# Input_1.net
KiCad netlist of a schematic drawn in Altium Designer
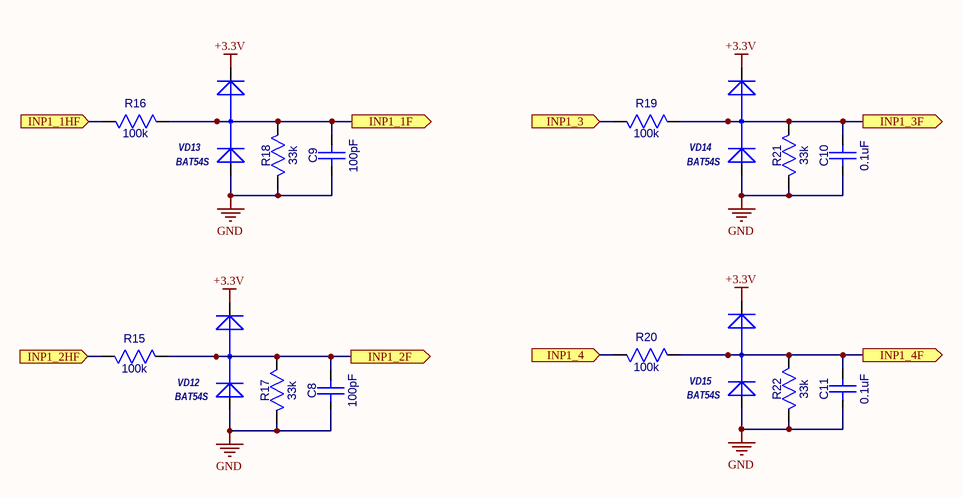
[diagram p0: Input_1.SchDoc]

(export (version "E")
  (design (tool "Eeschema 10.0.6"))
  (components
    (comp (ref "C8")
      (value "100pF")
      (footprint "CC0603-3M")
      (description "CC0603")
      (libsource (lib "*") (part "CC0603"))
    )
    (comp (ref "C9")
      (value "100pF")
      (footprint "CC0603-3M")
      (description "CC0603")
      (libsource (lib "*") (part "CC0603"))
    )
    (comp (ref "C10")
      (value "0.1uF")
      (footprint "CC0603-3M")
      (description "CC0603")
      (libsource (lib "*") (part "CC0603"))
    )
    (comp (ref "C11")
      (value "0.1uF")
      (footprint "CC0603-3M")
      (description "CC0603")
      (libsource (lib "*") (part "CC0603"))
    )
    (comp (ref "R15")
      (value "100k")
      (footprint "RC0603-3M")
      (description "RC0603")
      (libsource (lib "*") (part "RC0603"))
    )
    (comp (ref "R16")
      (value "100k")
      (footprint "RC0603-3M")
      (description "RC0603")
      (libsource (lib "*") (part "RC0603"))
    )
    (comp (ref "R17")
      (value "33k")
      (footprint "RC0603-3M")
      (description "RC0603")
      (libsource (lib "*") (part "RC0603"))
    )
    (comp (ref "R18")
      (value "33k")
      (footprint "RC0603-3M")
      (description "RC0603")
      (libsource (lib "*") (part "RC0603"))
    )
    (comp (ref "R19")
      (value "100k")
      (footprint "RC0603-3M")
      (description "RC0603")
      (libsource (lib "*") (part "RC0603"))
    )
    (comp (ref "R20")
      (value "100k")
      (footprint "RC0603-3M")
      (description "RC0603")
      (libsource (lib "*") (part "RC0603"))
    )
    (comp (ref "R21")
      (value "33k")
      (footprint "RC0603-3M")
      (description "RC0603")
      (libsource (lib "*") (part "RC0603"))
    )
    (comp (ref "R22")
      (value "33k")
      (footprint "RC0603-3M")
      (description "RC0603")
      (libsource (lib "*") (part "RC0603"))
    )
    (comp (ref "VD12") (value "BAT54S") (footprint "SOT-23(GSD)") (libsource (lib "*") (part "BAT54S")))
    (comp (ref "VD13") (value "BAT54S") (footprint "SOT-23(GSD)") (libsource (lib "*") (part "BAT54S")))
    (comp (ref "VD14") (value "BAT54S") (footprint "SOT-23(GSD)") (libsource (lib "*") (part "BAT54S")))
    (comp (ref "VD15") (value "BAT54S") (footprint "SOT-23(GSD)") (libsource (lib "*") (part "BAT54S")))
  )
  (nets
    (net (code "1") (name "+3.3V") (class "Default")
      (node (ref "VD12") (pin "2") (pinfunction "K_2") (pintype "passive"))
      (node (ref "VD13") (pin "2") (pinfunction "K_2") (pintype "passive"))
      (node (ref "VD14") (pin "2") (pinfunction "K_2") (pintype "passive"))
      (node (ref "VD15") (pin "2") (pinfunction "K_2") (pintype "passive"))
    )
    (net (code "2") (name "/INP1_1F") (class "Default")
      (node (ref "C9") (pin "2") (pinfunction "B_2") (pintype "passive"))
      (node (ref "R16") (pin "1") (pinfunction "A_1") (pintype "passive"))
      (node (ref "R18") (pin "1") (pinfunction "A_1") (pintype "passive"))
      (node (ref "VD13") (pin "3") (pinfunction "AK_3") (pintype "passive"))
    )
    (net (code "3") (name "/INP1_1HF") (class "Default")
      (node (ref "R16") (pin "2") (pinfunction "B_2") (pintype "passive"))
    )
    (net (code "4") (name "/INP1_2F") (class "Default")
      (node (ref "C8") (pin "2") (pinfunction "B_2") (pintype "passive"))
      (node (ref "R15") (pin "1") (pinfunction "A_1") (pintype "passive"))
      (node (ref "R17") (pin "1") (pinfunction "A_1") (pintype "passive"))
      (node (ref "VD12") (pin "3") (pinfunction "AK_3") (pintype "passive"))
    )
    (net (code "5") (name "/INP1_2HF") (class "Default")
      (node (ref "R15") (pin "2") (pinfunction "B_2") (pintype "passive"))
    )
    (net (code "6") (name "/INP1_3") (class "Default")
      (node (ref "R19") (pin "2") (pinfunction "B_2") (pintype "passive"))
    )
    (net (code "7") (name "/INP1_3F") (class "Default")
      (node (ref "C10") (pin "2") (pinfunction "B_2") (pintype "passive"))
      (node (ref "R19") (pin "1") (pinfunction "A_1") (pintype "passive"))
      (node (ref "R21") (pin "1") (pinfunction "A_1") (pintype "passive"))
      (node (ref "VD14") (pin "3") (pinfunction "AK_3") (pintype "passive"))
    )
    (net (code "8") (name "/INP1_4") (class "Default")
      (node (ref "R20") (pin "2") (pinfunction "B_2") (pintype "passive"))
    )
    (net (code "9") (name "/INP1_4F") (class "Default")
      (node (ref "C11") (pin "2") (pinfunction "B_2") (pintype "passive"))
      (node (ref "R20") (pin "1") (pinfunction "A_1") (pintype "passive"))
      (node (ref "R22") (pin "1") (pinfunction "A_1") (pintype "passive"))
      (node (ref "VD15") (pin "3") (pinfunction "AK_3") (pintype "passive"))
    )
    (net (code "10") (name "GND") (class "Default")
      (node (ref "C10") (pin "1") (pinfunction "A_1") (pintype "passive"))
      (node (ref "C11") (pin "1") (pinfunction "A_1") (pintype "passive"))
      (node (ref "C8") (pin "1") (pinfunction "A_1") (pintype "passive"))
      (node (ref "C9") (pin "1") (pinfunction "A_1") (pintype "passive"))
      (node (ref "R17") (pin "2") (pinfunction "B_2") (pintype "passive"))
      (node (ref "R18") (pin "2") (pinfunction "B_2") (pintype "passive"))
      (node (ref "R21") (pin "2") (pinfunction "B_2") (pintype "passive"))
      (node (ref "R22") (pin "2") (pinfunction "B_2") (pintype "passive"))
      (node (ref "VD12") (pin "1") (pinfunction "A_1") (pintype "passive"))
      (node (ref "VD13") (pin "1") (pinfunction "A_1") (pintype "passive"))
      (node (ref "VD14") (pin "1") (pinfunction "A_1") (pintype "passive"))
      (node (ref "VD15") (pin "1") (pinfunction "A_1") (pintype "passive"))
    )
  )
)
